# FTDI.net
KiCad netlist of a schematic drawn in Altium Designer
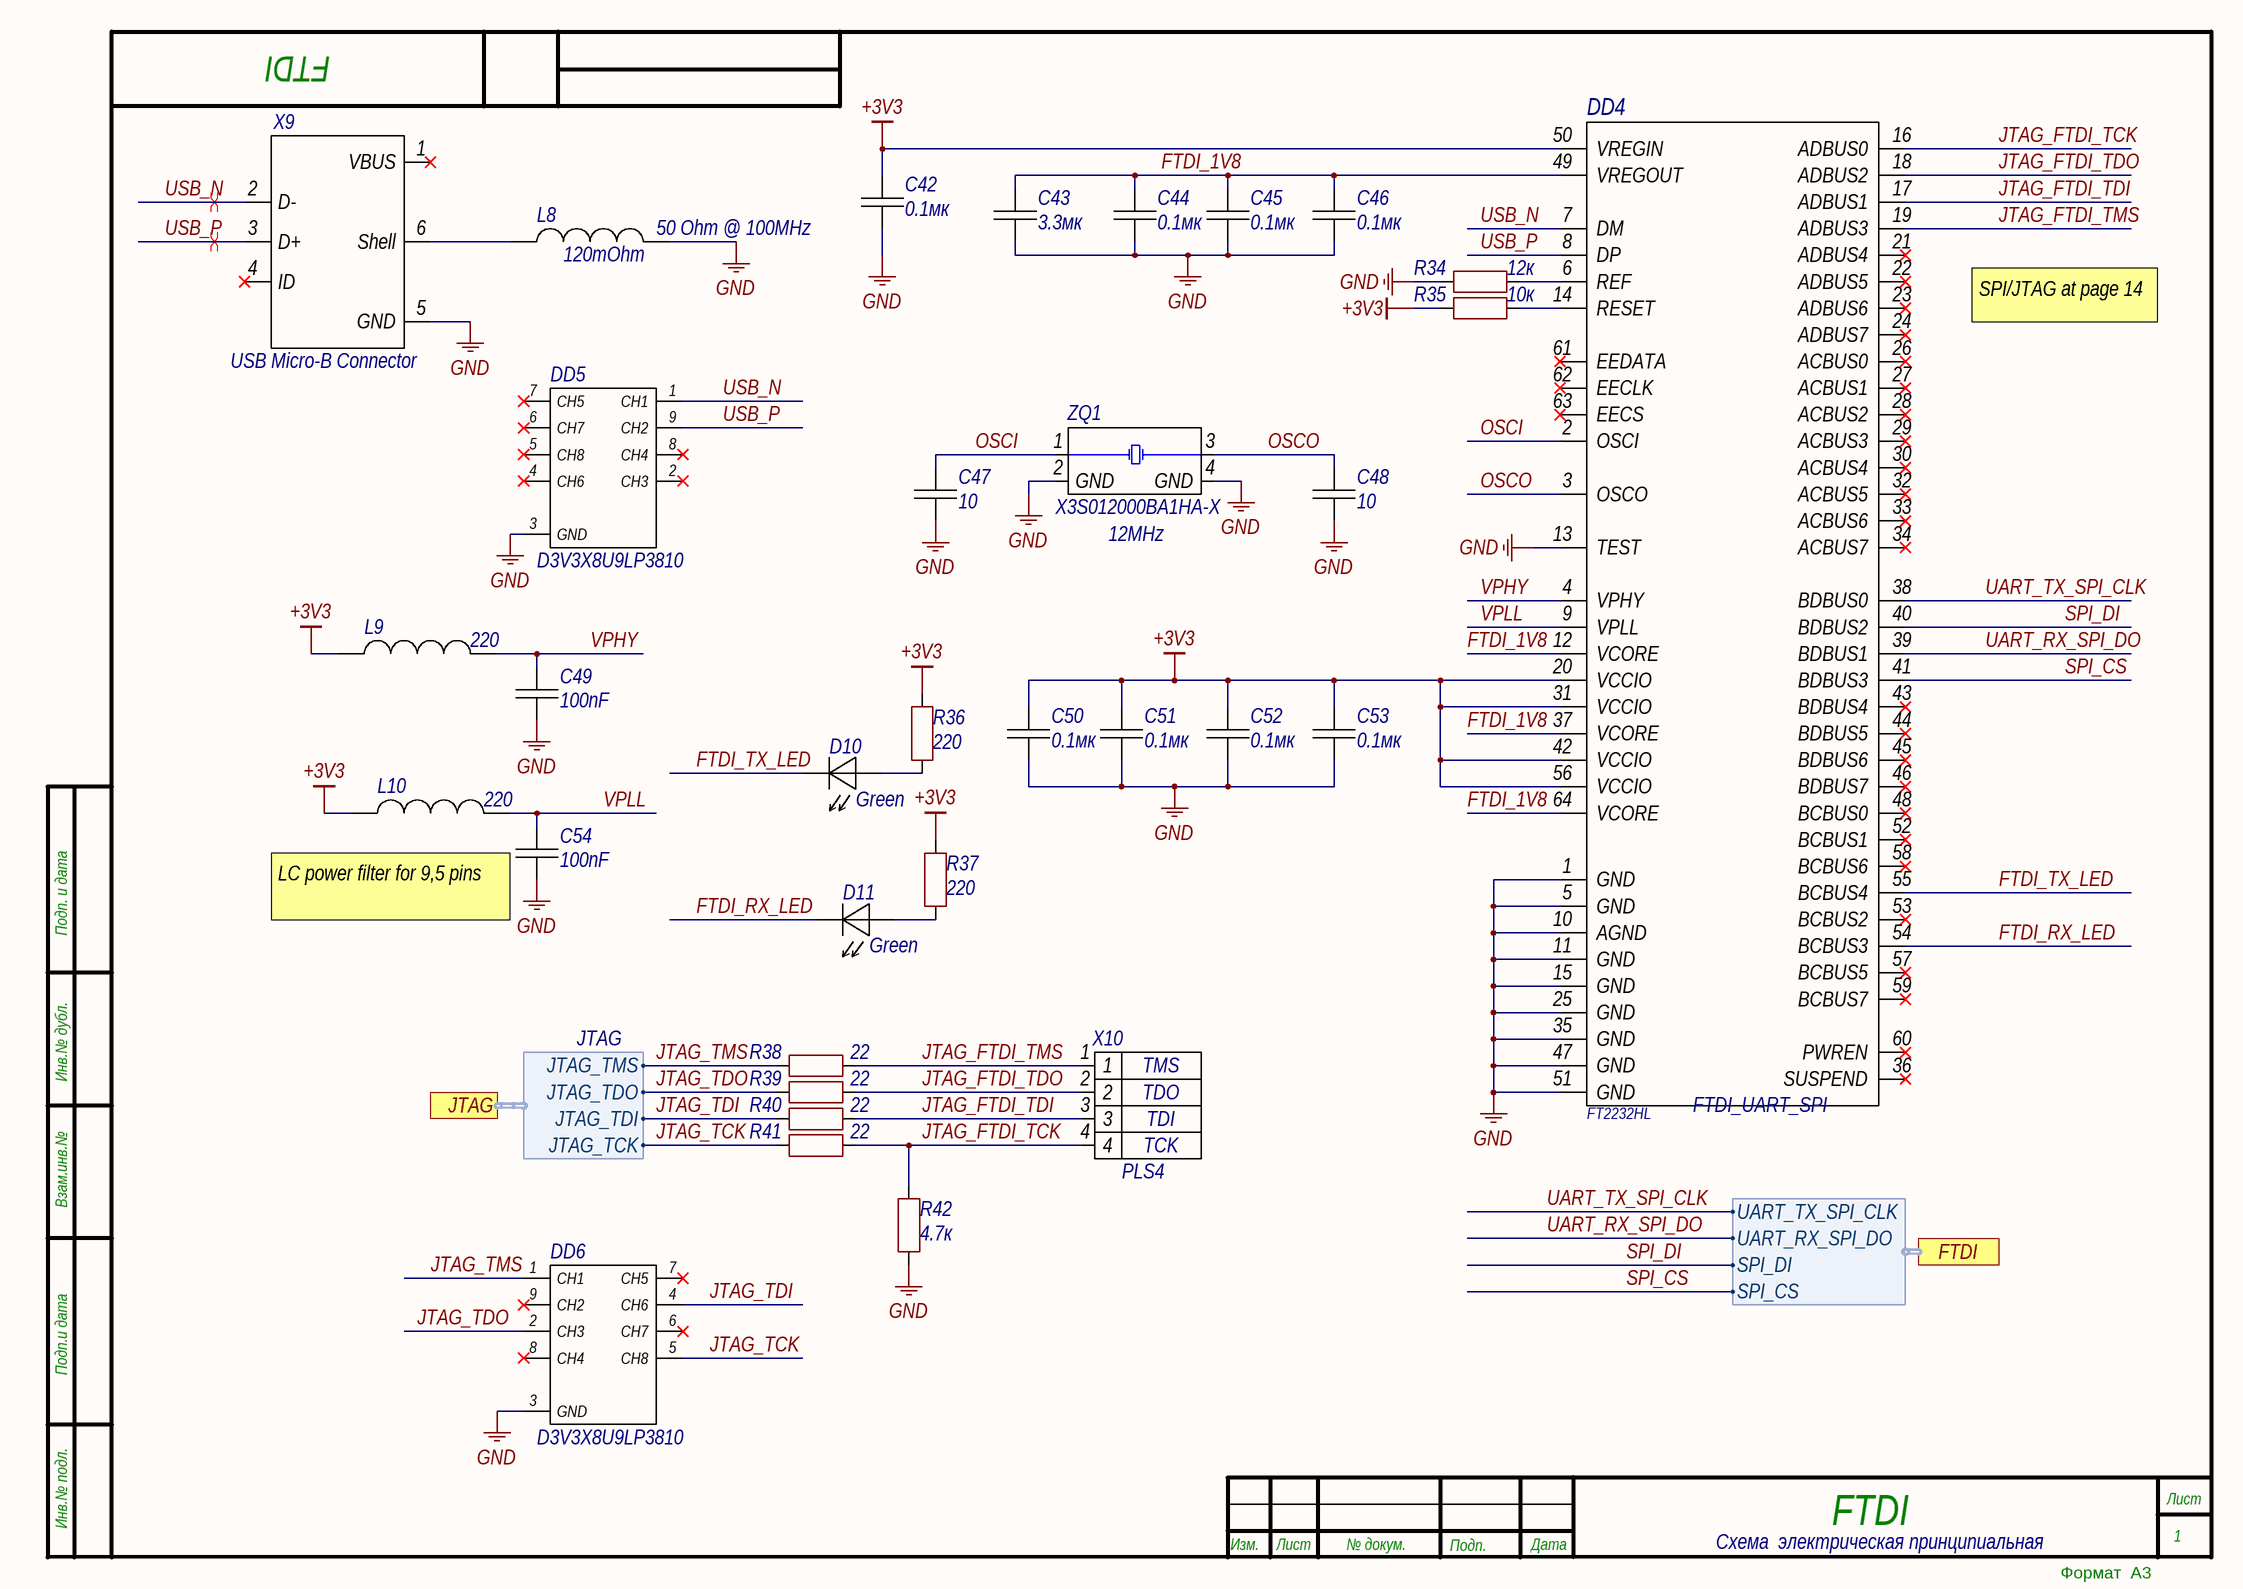
[diagram p0: FTDI.SchDoc]

(export (version "E")
  (design (tool "Eeschema 10.0.6"))
  (components
    (comp (ref "C42")
      (value "0.1мк")
      (footprint "CAP0402")
      (fields
        (field (name "MANUFACTURER") "Samsung Electro-Mechanics")
        (field (name "MPN") "CL05B104KB54PNC")
        (field (name "TOLERANCE") "10%")
      )
      (libsource (lib "Library") (part "CAPC"))
    )
    (comp (ref "C43")
      (value "3.3мк")
      (footprint "CAP0402")
      (fields
        (field (name "MANUFACTURER") "TDK")
        (field (name "MPN") "C1005X5R0J335MTJ00E")
        (field (name "VOLTAGE") "6.3V")
      )
      (libsource (lib "Library") (part "CAPC"))
    )
    (comp (ref "C44")
      (value "0.1мк")
      (footprint "CAP0402")
      (fields
        (field (name "MANUFACTURER") "Samsung Electro-Mechanics")
        (field (name "MPN") "CL05B104KB54PNC")
        (field (name "TOLERANCE") "10%")
      )
      (libsource (lib "Library") (part "CAPC"))
    )
    (comp (ref "C45")
      (value "0.1мк")
      (footprint "CAP0402")
      (fields
        (field (name "MANUFACTURER") "Samsung Electro-Mechanics")
        (field (name "MPN") "CL05B104KB54PNC")
        (field (name "TOLERANCE") "10%")
      )
      (libsource (lib "Library") (part "CAPC"))
    )
    (comp (ref "C46")
      (value "0.1мк")
      (footprint "CAP0402")
      (fields
        (field (name "MANUFACTURER") "Samsung Electro-Mechanics")
        (field (name "MPN") "CL05B104KB54PNC")
        (field (name "TOLERANCE") "10%")
      )
      (libsource (lib "Library") (part "CAPC"))
    )
    (comp (ref "C47")
      (value "10")
      (footprint "CAP0402")
      (fields
        (field (name "MANUFACTURER") "Samsung Electro-Mechanics")
        (field (name "MPN") "CL05C100JB5NNNC")
        (field (name "VOLTAGE") "50V")
      )
      (libsource (lib "Library") (part "CAPC"))
    )
    (comp (ref "C48")
      (value "10")
      (footprint "CAP0402")
      (fields
        (field (name "MANUFACTURER") "Samsung Electro-Mechanics")
        (field (name "MPN") "CL05C100JB5NNNC")
        (field (name "VOLTAGE") "50V")
      )
      (libsource (lib "Library") (part "CAPC"))
    )
    (comp (ref "C49")
      (value "100nF")
      (footprint "CAP0402")
      (fields
        (field (name "MANUFACTURER") "Samsung Electro-Mechanics")
        (field (name "MPN") "CL05B104KB54PNC")
        (field (name "TOLERANCE") "10%")
      )
      (libsource (lib "Library") (part "CAPC"))
    )
    (comp (ref "C50")
      (value "0.1мк")
      (footprint "CAP0402")
      (fields
        (field (name "MANUFACTURER") "Samsung Electro-Mechanics")
        (field (name "MPN") "CL05B104KB54PNC")
        (field (name "TOLERANCE") "10%")
      )
      (libsource (lib "Library") (part "CAPC"))
    )
    (comp (ref "C51")
      (value "0.1мк")
      (footprint "CAP0402")
      (fields
        (field (name "MANUFACTURER") "Samsung Electro-Mechanics")
        (field (name "MPN") "CL05B104KB54PNC")
        (field (name "TOLERANCE") "10%")
      )
      (libsource (lib "Library") (part "CAPC"))
    )
    (comp (ref "C52")
      (value "0.1мк")
      (footprint "CAP0402")
      (fields
        (field (name "MANUFACTURER") "Samsung Electro-Mechanics")
        (field (name "MPN") "CL05B104KB54PNC")
        (field (name "TOLERANCE") "10%")
      )
      (libsource (lib "Library") (part "CAPC"))
    )
    (comp (ref "C53")
      (value "0.1мк")
      (footprint "CAP0402")
      (fields
        (field (name "MANUFACTURER") "Samsung Electro-Mechanics")
        (field (name "MPN") "CL05B104KB54PNC")
        (field (name "TOLERANCE") "10%")
      )
      (libsource (lib "Library") (part "CAPC"))
    )
    (comp (ref "C54")
      (value "100nF")
      (footprint "CAP0402")
      (fields
        (field (name "MANUFACTURER") "Samsung Electro-Mechanics")
        (field (name "MPN") "CL05B104KB54PNC")
        (field (name "TOLERANCE") "10%")
      )
      (libsource (lib "Library") (part "CAPC"))
    )
    (comp (ref "D10")
      (value "Green")
      (footprint "LED603")
      (fields
        (field (name "MANUFACTURER") "Everlight Elec")
        (field (name "MPN") "19-217/GHC-YR1S2/3T")
        (field (name "PART NUMBER") "LEDC")
      )
      (libsource (lib "Library") (part "LEDC"))
    )
    (comp (ref "D11")
      (value "Green")
      (footprint "LED603")
      (fields
        (field (name "MANUFACTURER") "Everlight Elec")
        (field (name "MPN") "19-217/GHC-YR1S2/3T")
        (field (name "PART NUMBER") "LEDC")
      )
      (libsource (lib "Library") (part "LEDC"))
    )
    (comp (ref "DD4")
      (value "~")
      (footprint "LQFP64")
      (fields
        (field (name "MPN") "FT2232HL")
        (field (name "PART NUMBER") "FT2232HL")
        (field (name "MANUFACTURER") "FTDI")
      )
      (libsource (lib "Library") (part "DD_FT2232HL"))
    )
    (comp (ref "DD5")
      (value "TVS at USB diff pair")
      (footprint "U-DFN3810-9")
      (fields
        (field (name "MPN") "D3V3X8U9LP3810")
        (field (name "PART NUMBER") "D3V3X8U9LP3810")
        (field (name "MANUFACTURER") "DiodesInc")
      )
      (libsource (lib "") (part "DD_D3V3X8U9LP3810_1"))
    )
    (comp (ref "DD6")
      (value "TVS Diode at JTAG")
      (footprint "U-DFN3810-9")
      (fields
        (field (name "MPN") "D3V3X8U9LP3810")
        (field (name "PART NUMBER") "D3V3X8U9LP3810")
        (field (name "MANUFACTURER") "DiodesInc")
      )
      (libsource (lib "Library") (part "DD_D3V3X8U9LP3810"))
    )
    (comp (ref "L8")
      (value "50 Ohm @ 100MHz")
      (footprint "CAPC0603N")
      (fields
        (field (name "MANUFACTURER") "FH(Guangdong Fenghua Advanced Tech)")
        (field (name "MPN") "CBW160808U500T")
        (field (name "PART NUMBER") "Inductor_SMD")
        (field (name "DCRESISTANCE") "120mOhm")
      )
      (libsource (lib "Library") (part "Inductor"))
    )
    (comp (ref "L9")
      (value "220")
      (footprint "CAPC0603N")
      (fields
        (field (name "MANUFACTURER") "Murata")
        (field (name "MPN") "BLM18KG221SN1D")
        (field (name "TOLERANCE") "25%")
      )
      (libsource (lib "Library") (part "Inductor"))
    )
    (comp (ref "L10")
      (value "220")
      (footprint "CAPC0603N")
      (fields
        (field (name "MANUFACTURER") "Murata")
        (field (name "MPN") "BLM18KG221SN1D")
        (field (name "TOLERANCE") "25%")
      )
      (libsource (lib "Library") (part "Inductor"))
    )
    (comp (ref "R34")
      (value "12к")
      (footprint "RESC0402(1005)_M")
      (fields
        (field (name "MANUFACTURER") "UNI-ROYAL(Uniroyal Elec)")
        (field (name "MPN") "0402WGF1202TCE")
        (field (name "PART NUMBER") "RES0402")
      )
      (libsource (lib "") (part "RES_3"))
    )
    (comp (ref "R35")
      (value "10к")
      (footprint "RESC0402(1005)_M")
      (fields
        (field (name "MANUFACTURER") "UNI-ROYAL(Uniroyal Elec)")
        (field (name "MPN") "0402WGF1002TCE")
        (field (name "PART NUMBER") "RES0402")
      )
      (libsource (lib "") (part "RES_3"))
    )
    (comp (ref "R36")
      (value "220")
      (footprint "RESC0402(1005)_M")
      (fields
        (field (name "MANUFACTURER") "UNI-ROYAL(Uniroyal Elec)")
        (field (name "MPN") "0402WGF2200TCE")
        (field (name "PART NUMBER") "RES0402")
      )
      (libsource (lib "") (part "RES_1"))
    )
    (comp (ref "R37")
      (value "220")
      (footprint "RESC0402(1005)_M")
      (fields
        (field (name "MANUFACTURER") "UNI-ROYAL(Uniroyal Elec)")
        (field (name "MPN") "0402WGF2200TCE")
        (field (name "PART NUMBER") "RES0402")
      )
      (libsource (lib "") (part "RES_1"))
    )
    (comp (ref "R38")
      (value "22")
      (footprint "RESC0402(1005)_M")
      (fields
        (field (name "MANUFACTURER") "UNI-ROYAL")
        (field (name "MPN") "0402WGF220JTCE")
        (field (name "POWER") "1/16W")
      )
      (libsource (lib "Library") (part "RES"))
    )
    (comp (ref "R39")
      (value "22")
      (footprint "RESC0402(1005)_M")
      (fields
        (field (name "MANUFACTURER") "UNI-ROYAL")
        (field (name "MPN") "0402WGF220JTCE")
        (field (name "POWER") "1/16W")
      )
      (libsource (lib "Library") (part "RES"))
    )
    (comp (ref "R40")
      (value "22")
      (footprint "RESC0402(1005)_M")
      (fields
        (field (name "MANUFACTURER") "UNI-ROYAL")
        (field (name "MPN") "0402WGF220JTCE")
        (field (name "POWER") "1/16W")
      )
      (libsource (lib "Library") (part "RES"))
    )
    (comp (ref "R41")
      (value "22")
      (footprint "RESC0402(1005)_M")
      (fields
        (field (name "MANUFACTURER") "UNI-ROYAL")
        (field (name "MPN") "0402WGF220JTCE")
        (field (name "POWER") "1/16W")
      )
      (libsource (lib "Library") (part "RES"))
    )
    (comp (ref "R42")
      (value "4.7к")
      (footprint "RESC0402(1005)_M")
      (fields
        (field (name "MANUFACTURER") "UNI-ROYAL")
        (field (name "MPN") "0402WGF4701TCE")
        (field (name "POWER") "1/16W")
      )
      (libsource (lib "") (part "RES_2"))
    )
    (comp (ref "X9")
      (value "USB Micro-B Connector")
      (footprint "AMPHENOL_10118194-0001LF")
      (description "USB 2.0 Micro-B Female Connector")
      (fields (field (name "PART NUMBER") "10118194-0001LF") (field (name "MANUFACTURER") "Amphenol"))
      (libsource (lib "Library") (part "USB_Micro_B"))
    )
    (comp (ref "X10")
      (value "PLS4")
      (footprint "PLS4")
      (description "JTAG Header")
      (fields
        (field (name "MPN") "PLS4")
        (field (name "WIRE1") "TMS")
        (field (name "WIRE2") "TDO")
        (field (name "WIRE3") "TDI")
        (field (name "WIRE4") "TCK")
      )
      (libsource (lib "Library") (part "PLS4"))
    )
    (comp (ref "ZQ1")
      (value "12MHz")
      (footprint "TSX-3225_V")
      (fields
        (field (name "MPN") "X3S012000BA1HA-X")
        (field (name "PART NUMBER") "X3S012000BA1HA-X")
        (field (name "MANUFACTURER") "HELE(HARMONY ELEC)")
      )
      (libsource (lib "Library") (part "Crystal_TSX-3225_24M"))
    )
  )
  (nets
    (net (code "3") (name "+3V3") (class "Default")
      (node (ref "C42") (pin "1") (pinfunction "1_1") (pintype "passive"))
      (node (ref "C50") (pin "2") (pinfunction "2_2") (pintype "passive"))
      (node (ref "C51") (pin "2") (pinfunction "2_2") (pintype "passive"))
      (node (ref "C52") (pin "2") (pinfunction "2_2") (pintype "passive"))
      (node (ref "C53") (pin "2") (pinfunction "2_2") (pintype "passive"))
      (node (ref "DD4") (pin "20") (pinfunction "VCCIO_20") (pintype "passive"))
      (node (ref "DD4") (pin "31") (pinfunction "VCCIO_31") (pintype "passive"))
      (node (ref "DD4") (pin "42") (pinfunction "VCCIO_42") (pintype "passive"))
      (node (ref "DD4") (pin "50") (pinfunction "VREGIN_50") (pintype "passive"))
      (node (ref "DD4") (pin "56") (pinfunction "VCCIO_56") (pintype "passive"))
      (node (ref "L10") (pin "1") (pinfunction "1_1") (pintype "passive"))
      (node (ref "L9") (pin "1") (pinfunction "1_1") (pintype "passive"))
      (node (ref "R35") (pin "2") (pinfunction "2_2") (pintype "passive"))
      (node (ref "R36") (pin "2") (pinfunction "2_2") (pintype "passive"))
      (node (ref "R37") (pin "2") (pinfunction "2_2") (pintype "passive"))
    )
    (net (code "4") (name "/FTDI_1V8") (class "Default")
      (node (ref "C43") (pin "2") (pinfunction "2_2") (pintype "passive"))
      (node (ref "C44") (pin "1") (pinfunction "1_1") (pintype "passive"))
      (node (ref "C45") (pin "1") (pinfunction "1_1") (pintype "passive"))
      (node (ref "C46") (pin "1") (pinfunction "1_1") (pintype "passive"))
      (node (ref "DD4") (pin "12") (pinfunction "VCORE_12") (pintype "passive"))
      (node (ref "DD4") (pin "37") (pinfunction "VCORE_37") (pintype "passive"))
      (node (ref "DD4") (pin "49") (pinfunction "VREGOUT_49") (pintype "passive"))
      (node (ref "DD4") (pin "64") (pinfunction "VCORE_64") (pintype "passive"))
    )
    (net (code "5") (name "/FTDI_RX_LED") (class "Default")
      (node (ref "D11") (pin "1") (pinfunction "A_1") (pintype "passive"))
      (node (ref "DD4") (pin "54") (pinfunction "BCBUS3_54") (pintype "passive"))
    )
    (net (code "6") (name "/FTDI_TX_LED") (class "Default")
      (node (ref "D10") (pin "1") (pinfunction "A_1") (pintype "passive"))
      (node (ref "DD4") (pin "55") (pinfunction "BCBUS4_55") (pintype "passive"))
    )
    (net (code "7") (name "/JTAG_FTDI_TCK") (class "Default")
      (node (ref "DD4") (pin "16") (pinfunction "ADBUS0_16") (pintype "passive"))
      (node (ref "R41") (pin "2") (pinfunction "2_2") (pintype "passive"))
      (node (ref "R42") (pin "1") (pinfunction "1_1") (pintype "passive"))
      (node (ref "X10") (pin "4") (pinfunction "4_4") (pintype "passive"))
    )
    (net (code "8") (name "/JTAG_FTDI_TDI") (class "Default")
      (node (ref "DD4") (pin "17") (pinfunction "ADBUS1_17") (pintype "passive"))
      (node (ref "R40") (pin "2") (pinfunction "2_2") (pintype "passive"))
      (node (ref "X10") (pin "3") (pinfunction "3_3") (pintype "passive"))
    )
    (net (code "9") (name "/JTAG_FTDI_TDO") (class "Default")
      (node (ref "DD4") (pin "18") (pinfunction "ADBUS2_18") (pintype "passive"))
      (node (ref "R39") (pin "2") (pinfunction "2_2") (pintype "passive"))
      (node (ref "X10") (pin "2") (pinfunction "2_2") (pintype "passive"))
    )
    (net (code "10") (name "/JTAG_FTDI_TMS") (class "Default")
      (node (ref "DD4") (pin "19") (pinfunction "ADBUS3_19") (pintype "passive"))
      (node (ref "R38") (pin "2") (pinfunction "2_2") (pintype "passive"))
      (node (ref "X10") (pin "1") (pinfunction "1_1") (pintype "passive"))
    )
    (net (code "11") (name "/JTAG_TCK") (class "Default")
      (node (ref "DD6") (pin "5") (pinfunction "CH8_5") (pintype "passive"))
      (node (ref "R41") (pin "1") (pinfunction "1_1") (pintype "passive"))
    )
    (net (code "12") (name "/JTAG_TDI") (class "Default")
      (node (ref "DD6") (pin "4") (pinfunction "CH6_4") (pintype "passive"))
      (node (ref "R40") (pin "1") (pinfunction "1_1") (pintype "passive"))
    )
    (net (code "13") (name "/JTAG_TDO") (class "Default")
      (node (ref "DD6") (pin "2") (pinfunction "CH3_2") (pintype "passive"))
      (node (ref "R39") (pin "1") (pinfunction "1_1") (pintype "passive"))
    )
    (net (code "14") (name "/JTAG_TMS") (class "Default")
      (node (ref "DD6") (pin "1") (pinfunction "CH1_1") (pintype "passive"))
      (node (ref "R38") (pin "1") (pinfunction "1_1") (pintype "passive"))
    )
    (net (code "15") (name "/OSCI") (class "Default")
      (node (ref "C47") (pin "2") (pinfunction "2_2") (pintype "passive"))
      (node (ref "DD4") (pin "2") (pinfunction "OSCI_2") (pintype "passive"))
      (node (ref "ZQ1") (pin "1") (pinfunction "X1_1") (pintype "passive"))
    )
    (net (code "16") (name "/OSCO") (class "Default")
      (node (ref "C48") (pin "2") (pinfunction "2_2") (pintype "passive"))
      (node (ref "DD4") (pin "3") (pinfunction "OSCO_3") (pintype "passive"))
      (node (ref "ZQ1") (pin "3") (pinfunction "X2_3") (pintype "passive"))
    )
    (net (code "17") (name "/SPI_CS") (class "Default")
      (node (ref "DD4") (pin "41") (pinfunction "BDBUS3_41") (pintype "passive"))
    )
    (net (code "18") (name "/SPI_DI") (class "Default")
      (node (ref "DD4") (pin "40") (pinfunction "BDBUS2_40") (pintype "passive"))
    )
    (net (code "19") (name "/UART_RX_SPI_DO") (class "Default")
      (node (ref "DD4") (pin "39") (pinfunction "BDBUS1_39") (pintype "passive"))
    )
    (net (code "20") (name "/UART_TX_SPI_CLK") (class "Default")
      (node (ref "DD4") (pin "38") (pinfunction "BDBUS0_38") (pintype "passive"))
    )
    (net (code "21") (name "/USB_N") (class "Default")
      (node (ref "DD4") (pin "7") (pinfunction "DM_7") (pintype "passive"))
      (node (ref "DD5") (pin "1") (pinfunction "CH1_1") (pintype "passive"))
      (node (ref "X9") (pin "2") (pinfunction "D-_2") (pintype "passive"))
    )
    (net (code "22") (name "/USB_P") (class "Default")
      (node (ref "DD4") (pin "8") (pinfunction "DP_8") (pintype "passive"))
      (node (ref "DD5") (pin "9") (pinfunction "CH2_9") (pintype "passive"))
      (node (ref "X9") (pin "3") (pinfunction "D+_3") (pintype "passive"))
    )
    (net (code "23") (name "/VPHY") (class "Default")
      (node (ref "C49") (pin "2") (pinfunction "2_2") (pintype "passive"))
      (node (ref "DD4") (pin "4") (pinfunction "VPHY_4") (pintype "passive"))
      (node (ref "L9") (pin "2") (pinfunction "2_2") (pintype "passive"))
    )
    (net (code "24") (name "/VPLL") (class "Default")
      (node (ref "C54") (pin "2") (pinfunction "2_2") (pintype "passive"))
      (node (ref "DD4") (pin "9") (pinfunction "VPLL_9") (pintype "passive"))
      (node (ref "L10") (pin "2") (pinfunction "2_2") (pintype "passive"))
    )
    (net (code "27") (name "GND") (class "Default")
      (node (ref "C42") (pin "2") (pinfunction "2_2") (pintype "passive"))
      (node (ref "C43") (pin "1") (pinfunction "1_1") (pintype "passive"))
      (node (ref "C44") (pin "2") (pinfunction "2_2") (pintype "passive"))
      (node (ref "C45") (pin "2") (pinfunction "2_2") (pintype "passive"))
      (node (ref "C46") (pin "2") (pinfunction "2_2") (pintype "passive"))
      (node (ref "C47") (pin "1") (pinfunction "1_1") (pintype "passive"))
      (node (ref "C48") (pin "1") (pinfunction "1_1") (pintype "passive"))
      (node (ref "C49") (pin "1") (pinfunction "1_1") (pintype "passive"))
      (node (ref "C50") (pin "1") (pinfunction "1_1") (pintype "passive"))
      (node (ref "C51") (pin "1") (pinfunction "1_1") (pintype "passive"))
      (node (ref "C52") (pin "1") (pinfunction "1_1") (pintype "passive"))
      (node (ref "C53") (pin "1") (pinfunction "1_1") (pintype "passive"))
      (node (ref "C54") (pin "1") (pinfunction "1_1") (pintype "passive"))
      (node (ref "DD4") (pin "1") (pinfunction "GND_1") (pintype "passive"))
      (node (ref "DD4") (pin "10") (pinfunction "AGND_10") (pintype "passive"))
      (node (ref "DD4") (pin "11") (pinfunction "GND_11") (pintype "passive"))
      (node (ref "DD4") (pin "13") (pinfunction "TEST_13") (pintype "passive"))
      (node (ref "DD4") (pin "15") (pinfunction "GND_15") (pintype "passive"))
      (node (ref "DD4") (pin "25") (pinfunction "GND_25") (pintype "passive"))
      (node (ref "DD4") (pin "35") (pinfunction "GND_35") (pintype "passive"))
      (node (ref "DD4") (pin "47") (pinfunction "GND_47") (pintype "passive"))
      (node (ref "DD4") (pin "5") (pinfunction "GND_5") (pintype "passive"))
      (node (ref "DD4") (pin "51") (pinfunction "GND_51") (pintype "passive"))
      (node (ref "DD5") (pin "3") (pinfunction "GND_3") (pintype "passive"))
      (node (ref "DD6") (pin "3") (pinfunction "GND_3") (pintype "passive"))
      (node (ref "L8") (pin "2") (pinfunction "2_2") (pintype "passive"))
      (node (ref "R34") (pin "2") (pinfunction "2_2") (pintype "passive"))
      (node (ref "R42") (pin "2") (pinfunction "2_2") (pintype "passive"))
      (node (ref "X9") (pin "5") (pinfunction "GND_5") (pintype "passive"))
      (node (ref "ZQ1") (pin "2") (pinfunction "GND_2") (pintype "power_in"))
      (node (ref "ZQ1") (pin "4") (pinfunction "GND_4") (pintype "power_in"))
    )
    (net (code "28") (name "Net-(D10-K)") (class "Default")
      (node (ref "D10") (pin "2") (pinfunction "K_2") (pintype "passive"))
      (node (ref "R36") (pin "1") (pinfunction "1_1") (pintype "passive"))
    )
    (net (code "29") (name "Net-(D11-K)") (class "Default")
      (node (ref "D11") (pin "2") (pinfunction "K_2") (pintype "passive"))
      (node (ref "R37") (pin "1") (pinfunction "1_1") (pintype "passive"))
    )
    (net (code "30") (name "Net-(DD4-REF)") (class "Default")
      (node (ref "DD4") (pin "6") (pinfunction "REF_6") (pintype "passive"))
      (node (ref "R34") (pin "1") (pinfunction "1_1") (pintype "passive"))
    )
    (net (code "31") (name "Net-(DD4-RESET)") (class "Default")
      (node (ref "DD4") (pin "14") (pinfunction "RESET_14") (pintype "passive"))
      (node (ref "R35") (pin "1") (pinfunction "1_1") (pintype "passive"))
    )
    (net (code "32") (name "Net-(X9-Shell)") (class "Default")
      (node (ref "L8") (pin "1") (pinfunction "1_1") (pintype "passive"))
      (node (ref "X9") (pin "6") (pinfunction "Shell_6") (pintype "passive"))
    )
    (net (code "33") (name "unconnected-(DD4-ACBUS0-Pad26)") (class "Default")
      (node (ref "DD4") (pin "26") (pinfunction "ACBUS0_26") (pintype "passive+no_connect"))
    )
    (net (code "34") (name "unconnected-(DD4-ACBUS1-Pad27)") (class "Default")
      (node (ref "DD4") (pin "27") (pinfunction "ACBUS1_27") (pintype "passive+no_connect"))
    )
    (net (code "35") (name "unconnected-(DD4-ACBUS2-Pad28)") (class "Default")
      (node (ref "DD4") (pin "28") (pinfunction "ACBUS2_28") (pintype "passive+no_connect"))
    )
    (net (code "36") (name "unconnected-(DD4-ACBUS3-Pad29)") (class "Default")
      (node (ref "DD4") (pin "29") (pinfunction "ACBUS3_29") (pintype "passive+no_connect"))
    )
    (net (code "37") (name "unconnected-(DD4-ACBUS4-Pad30)") (class "Default")
      (node (ref "DD4") (pin "30") (pinfunction "ACBUS4_30") (pintype "passive+no_connect"))
    )
    (net (code "38") (name "unconnected-(DD4-ACBUS5-Pad32)") (class "Default")
      (node (ref "DD4") (pin "32") (pinfunction "ACBUS5_32") (pintype "passive+no_connect"))
    )
    (net (code "39") (name "unconnected-(DD4-ACBUS6-Pad33)") (class "Default")
      (node (ref "DD4") (pin "33") (pinfunction "ACBUS6_33") (pintype "passive+no_connect"))
    )
    (net (code "40") (name "unconnected-(DD4-ACBUS7-Pad34)") (class "Default")
      (node (ref "DD4") (pin "34") (pinfunction "ACBUS7_34") (pintype "passive+no_connect"))
    )
    (net (code "41") (name "unconnected-(DD4-ADBUS4-Pad21)") (class "Default")
      (node (ref "DD4") (pin "21") (pinfunction "ADBUS4_21") (pintype "passive+no_connect"))
    )
    (net (code "42") (name "unconnected-(DD4-ADBUS5-Pad22)") (class "Default")
      (node (ref "DD4") (pin "22") (pinfunction "ADBUS5_22") (pintype "passive+no_connect"))
    )
    (net (code "43") (name "unconnected-(DD4-ADBUS6-Pad23)") (class "Default")
      (node (ref "DD4") (pin "23") (pinfunction "ADBUS6_23") (pintype "passive+no_connect"))
    )
    (net (code "44") (name "unconnected-(DD4-ADBUS7-Pad24)") (class "Default")
      (node (ref "DD4") (pin "24") (pinfunction "ADBUS7_24") (pintype "passive+no_connect"))
    )
    (net (code "45") (name "unconnected-(DD4-BCBUS0-Pad48)") (class "Default")
      (node (ref "DD4") (pin "48") (pinfunction "BCBUS0_48") (pintype "passive+no_connect"))
    )
    (net (code "46") (name "unconnected-(DD4-BCBUS1-Pad52)") (class "Default")
      (node (ref "DD4") (pin "52") (pinfunction "BCBUS1_52") (pintype "passive+no_connect"))
    )
    (net (code "47") (name "unconnected-(DD4-BCBUS2-Pad53)") (class "Default")
      (node (ref "DD4") (pin "53") (pinfunction "BCBUS2_53") (pintype "passive+no_connect"))
    )
    (net (code "48") (name "unconnected-(DD4-BCBUS5-Pad57)") (class "Default")
      (node (ref "DD4") (pin "57") (pinfunction "BCBUS5_57") (pintype "passive+no_connect"))
    )
    (net (code "49") (name "unconnected-(DD4-BCBUS6-Pad58)") (class "Default")
      (node (ref "DD4") (pin "58") (pinfunction "BCBUS6_58") (pintype "passive+no_connect"))
    )
    (net (code "50") (name "unconnected-(DD4-BCBUS7-Pad59)") (class "Default")
      (node (ref "DD4") (pin "59") (pinfunction "BCBUS7_59") (pintype "passive+no_connect"))
    )
    (net (code "51") (name "unconnected-(DD4-BDBUS4-Pad43)") (class "Default")
      (node (ref "DD4") (pin "43") (pinfunction "BDBUS4_43") (pintype "passive+no_connect"))
    )
    (net (code "52") (name "unconnected-(DD4-BDBUS5-Pad44)") (class "Default")
      (node (ref "DD4") (pin "44") (pinfunction "BDBUS5_44") (pintype "passive+no_connect"))
    )
    (net (code "53") (name "unconnected-(DD4-BDBUS6-Pad45)") (class "Default")
      (node (ref "DD4") (pin "45") (pinfunction "BDBUS6_45") (pintype "passive+no_connect"))
    )
    (net (code "54") (name "unconnected-(DD4-BDBUS7-Pad46)") (class "Default")
      (node (ref "DD4") (pin "46") (pinfunction "BDBUS7_46") (pintype "passive+no_connect"))
    )
    (net (code "55") (name "unconnected-(DD4-EECLK-Pad62)") (class "Default")
      (node (ref "DD4") (pin "62") (pinfunction "EECLK_62") (pintype "passive+no_connect"))
    )
    (net (code "56") (name "unconnected-(DD4-EECS-Pad63)") (class "Default")
      (node (ref "DD4") (pin "63") (pinfunction "EECS_63") (pintype "passive+no_connect"))
    )
    (net (code "57") (name "unconnected-(DD4-EEDATA-Pad61)") (class "Default")
      (node (ref "DD4") (pin "61") (pinfunction "EEDATA_61") (pintype "passive+no_connect"))
    )
    (net (code "58") (name "unconnected-(DD4-PWREN-Pad60)") (class "Default")
      (node (ref "DD4") (pin "60") (pinfunction "PWREN_60") (pintype "passive+no_connect"))
    )
    (net (code "59") (name "unconnected-(DD4-SUSPEND-Pad36)") (class "Default")
      (node (ref "DD4") (pin "36") (pinfunction "SUSPEND_36") (pintype "passive+no_connect"))
    )
    (net (code "60") (name "unconnected-(DD5-CH3-Pad2)") (class "Default")
      (node (ref "DD5") (pin "2") (pinfunction "CH3_2") (pintype "passive+no_connect"))
    )
    (net (code "61") (name "unconnected-(DD5-CH4-Pad8)") (class "Default")
      (node (ref "DD5") (pin "8") (pinfunction "CH4_8") (pintype "passive+no_connect"))
    )
    (net (code "62") (name "unconnected-(DD5-CH5-Pad7)") (class "Default")
      (node (ref "DD5") (pin "7") (pinfunction "CH5_7") (pintype "passive+no_connect"))
    )
    (net (code "63") (name "unconnected-(DD5-CH6-Pad4)") (class "Default")
      (node (ref "DD5") (pin "4") (pinfunction "CH6_4") (pintype "passive+no_connect"))
    )
    (net (code "64") (name "unconnected-(DD5-CH7-Pad6)") (class "Default")
      (node (ref "DD5") (pin "6") (pinfunction "CH7_6") (pintype "passive+no_connect"))
    )
    (net (code "65") (name "unconnected-(DD5-CH8-Pad5)") (class "Default")
      (node (ref "DD5") (pin "5") (pinfunction "CH8_5") (pintype "passive+no_connect"))
    )
    (net (code "66") (name "unconnected-(DD6-CH2-Pad9)") (class "Default")
      (node (ref "DD6") (pin "9") (pinfunction "CH2_9") (pintype "passive+no_connect"))
    )
    (net (code "67") (name "unconnected-(DD6-CH4-Pad8)") (class "Default")
      (node (ref "DD6") (pin "8") (pinfunction "CH4_8") (pintype "passive+no_connect"))
    )
    (net (code "68") (name "unconnected-(DD6-CH5-Pad7)") (class "Default")
      (node (ref "DD6") (pin "7") (pinfunction "CH5_7") (pintype "passive+no_connect"))
    )
    (net (code "69") (name "unconnected-(DD6-CH7-Pad6)") (class "Default")
      (node (ref "DD6") (pin "6") (pinfunction "CH7_6") (pintype "passive+no_connect"))
    )
    (net (code "70") (name "unconnected-(X9-ID-Pad4)") (class "Default")
      (node (ref "X9") (pin "4") (pinfunction "ID_4") (pintype "passive+no_connect"))
    )
    (net (code "71") (name "unconnected-(X9-VBUS-Pad1)") (class "Default")
      (node (ref "X9") (pin "1") (pinfunction "VBUS_1") (pintype "passive+no_connect"))
    )
  )
)
